# tube-control.net
KiCad netlist of a schematic drawn in Altium Designer
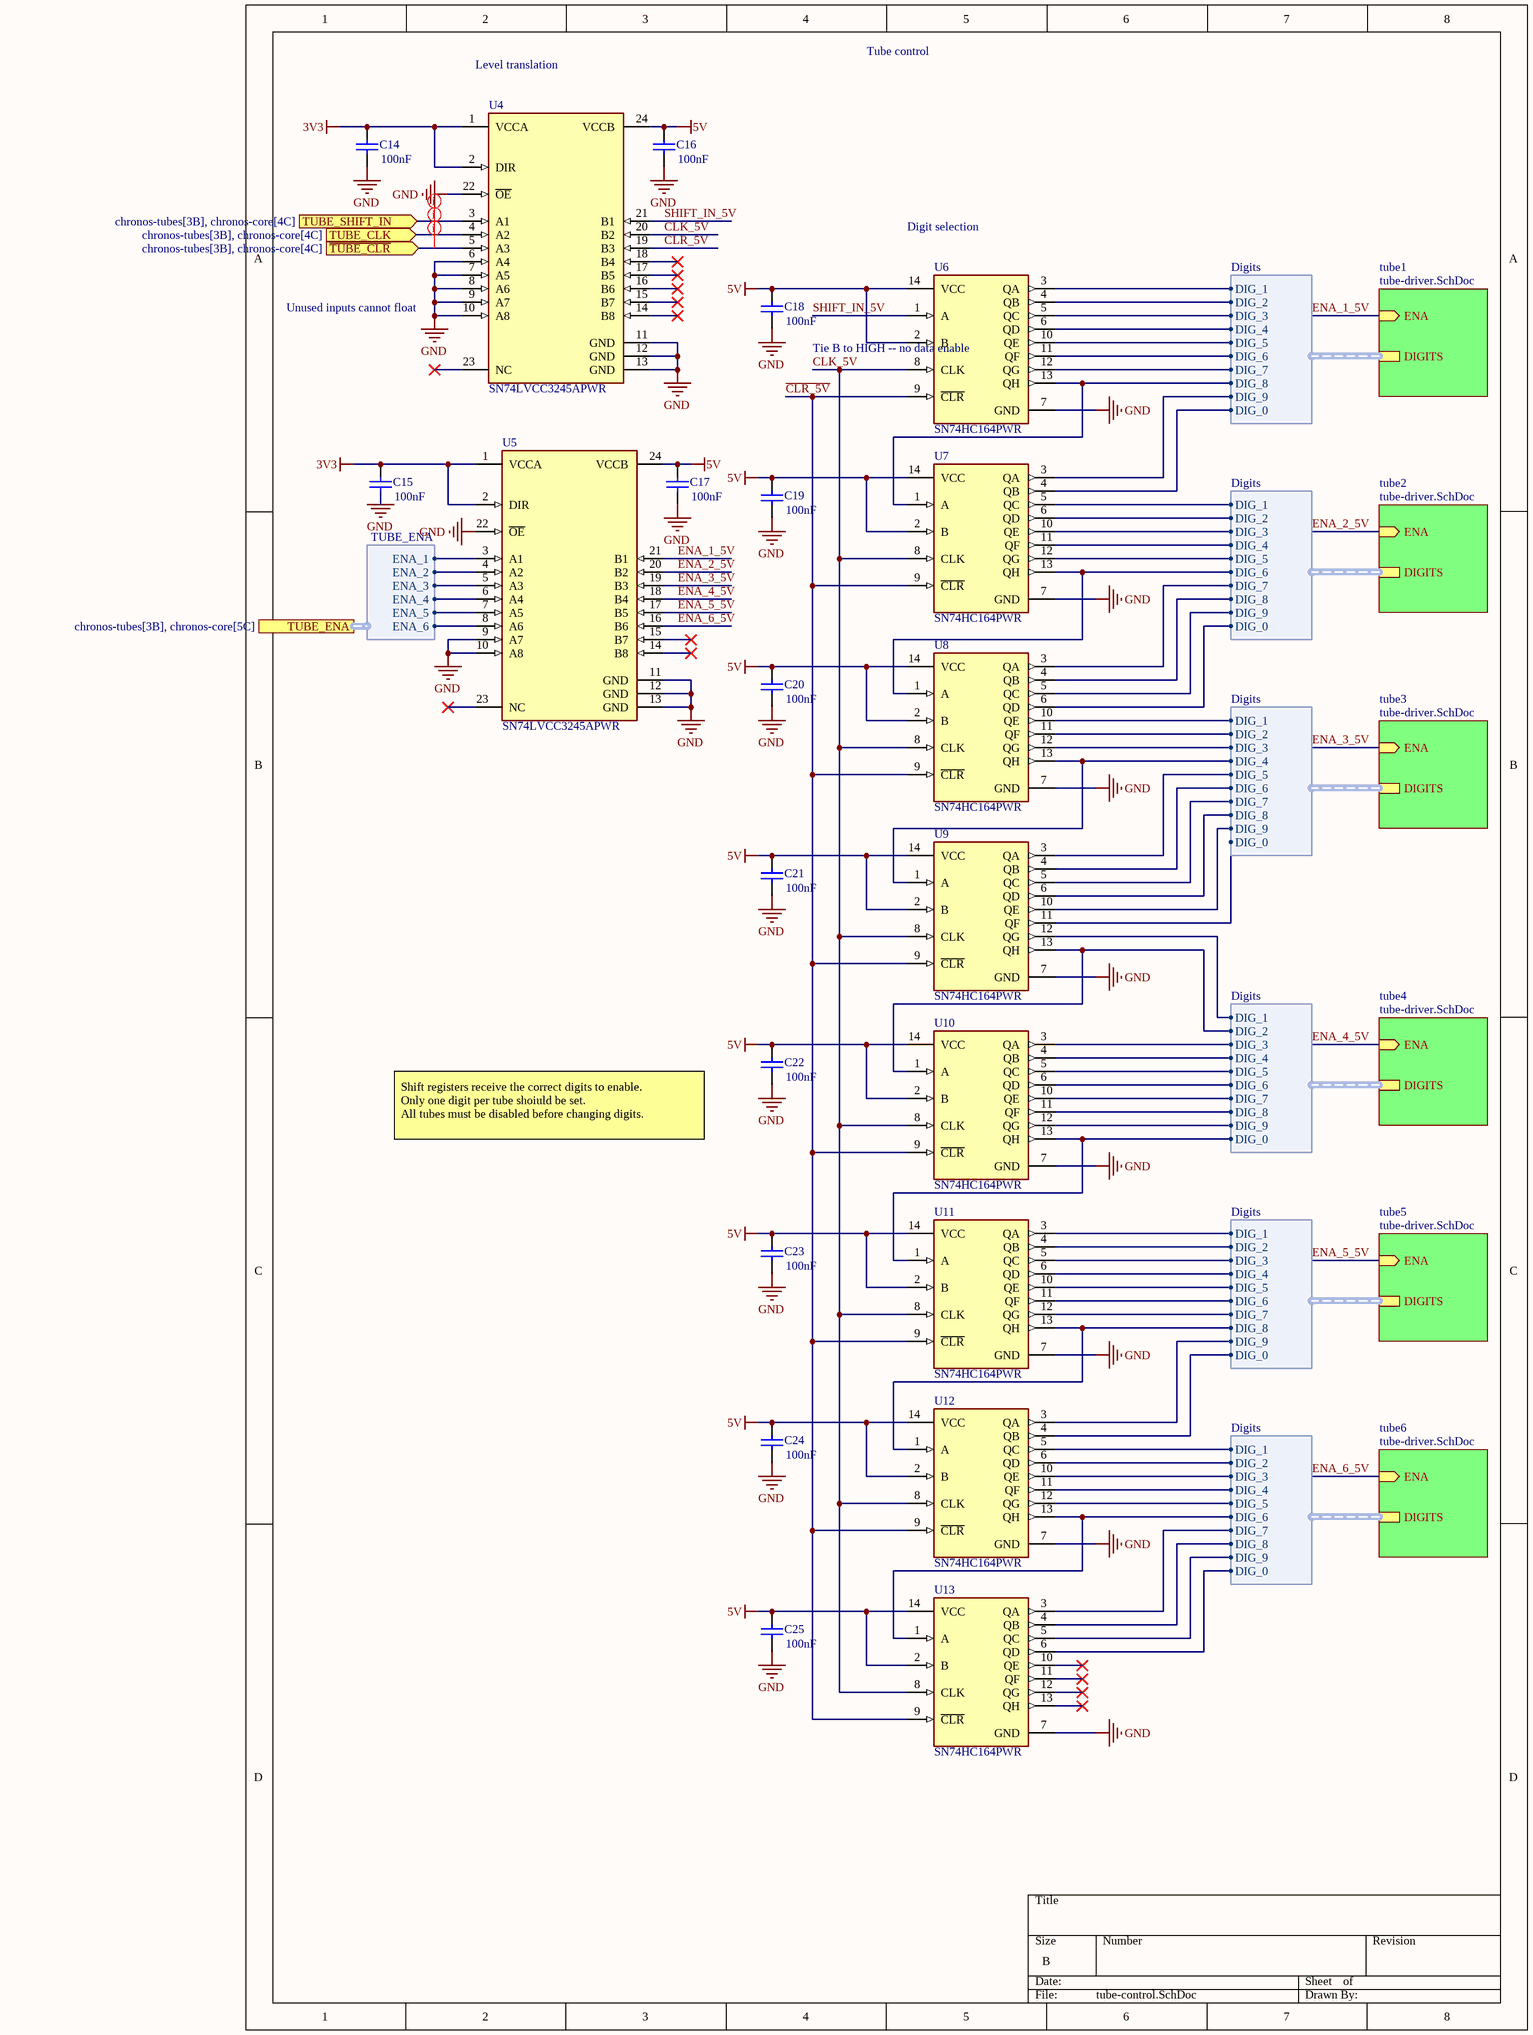
[diagram p0: tube-control.SchDoc]

(export (version "E")
  (design (tool "Eeschema 10.0.6"))
  (components
    (comp (ref "C14")
      (value "CL05B104KO5NNNC")
      (footprint "CAPC1050X55X23ML05T13")
      (description "Chip Capacitor, 100 nF, +/- 10%, 16 V, -55 to 125 degC, 0402 (1005 Metric), RoHS, Tape and Reel")
      (fields (field (name "MANUFACTURER") "Samsung Electro-Mechanics") (field (name "CAPACITANCE") "100nF"))
      (libsource (lib "Altium Content Vault") (part "CAP-NP-2"))
    )
    (comp (ref "C15")
      (value "CL05B104KO5NNNC")
      (footprint "CAPC1050X55X23ML05T13")
      (description "Chip Capacitor, 100 nF, +/- 10%, 16 V, -55 to 125 degC, 0402 (1005 Metric), RoHS, Tape and Reel")
      (fields (field (name "MANUFACTURER") "Samsung Electro-Mechanics") (field (name "CAPACITANCE") "100nF"))
      (libsource (lib "Altium Content Vault") (part "CAP-NP-2"))
    )
    (comp (ref "C16")
      (value "CL05B104KO5NNNC")
      (footprint "CAPC1050X55X23ML05T13")
      (description "Chip Capacitor, 100 nF, +/- 10%, 16 V, -55 to 125 degC, 0402 (1005 Metric), RoHS, Tape and Reel")
      (fields (field (name "MANUFACTURER") "Samsung Electro-Mechanics") (field (name "CAPACITANCE") "100nF"))
      (libsource (lib "Altium Content Vault") (part "CAP-NP-2"))
    )
    (comp (ref "C17")
      (value "CL05B104KO5NNNC")
      (footprint "CAPC1050X55X23ML05T13")
      (description "Chip Capacitor, 100 nF, +/- 10%, 16 V, -55 to 125 degC, 0402 (1005 Metric), RoHS, Tape and Reel")
      (fields (field (name "MANUFACTURER") "Samsung Electro-Mechanics") (field (name "CAPACITANCE") "100nF"))
      (libsource (lib "Altium Content Vault") (part "CAP-NP-2"))
    )
    (comp (ref "C18")
      (value "CL05B104KO5NNNC")
      (footprint "CAPC1050X55X23ML05T13")
      (description "Chip Capacitor, 100 nF, +/- 10%, 16 V, -55 to 125 degC, 0402 (1005 Metric), RoHS, Tape and Reel")
      (fields (field (name "MANUFACTURER") "Samsung Electro-Mechanics") (field (name "CAPACITANCE") "100nF"))
      (libsource (lib "Altium Content Vault") (part "CAP-NP-2"))
    )
    (comp (ref "C19")
      (value "CL05B104KO5NNNC")
      (footprint "CAPC1050X55X23ML05T13")
      (description "Chip Capacitor, 100 nF, +/- 10%, 16 V, -55 to 125 degC, 0402 (1005 Metric), RoHS, Tape and Reel")
      (fields (field (name "MANUFACTURER") "Samsung Electro-Mechanics") (field (name "CAPACITANCE") "100nF"))
      (libsource (lib "Altium Content Vault") (part "CAP-NP-2"))
    )
    (comp (ref "C20")
      (value "CL05B104KO5NNNC")
      (footprint "CAPC1050X55X23ML05T13")
      (description "Chip Capacitor, 100 nF, +/- 10%, 16 V, -55 to 125 degC, 0402 (1005 Metric), RoHS, Tape and Reel")
      (fields (field (name "MANUFACTURER") "Samsung Electro-Mechanics") (field (name "CAPACITANCE") "100nF"))
      (libsource (lib "Altium Content Vault") (part "CAP-NP-2"))
    )
    (comp (ref "C21")
      (value "CL05B104KO5NNNC")
      (footprint "CAPC1050X55X23ML05T13")
      (description "Chip Capacitor, 100 nF, +/- 10%, 16 V, -55 to 125 degC, 0402 (1005 Metric), RoHS, Tape and Reel")
      (fields (field (name "MANUFACTURER") "Samsung Electro-Mechanics") (field (name "CAPACITANCE") "100nF"))
      (libsource (lib "Altium Content Vault") (part "CAP-NP-2"))
    )
    (comp (ref "C22")
      (value "CL05B104KO5NNNC")
      (footprint "CAPC1050X55X23ML05T13")
      (description "Chip Capacitor, 100 nF, +/- 10%, 16 V, -55 to 125 degC, 0402 (1005 Metric), RoHS, Tape and Reel")
      (fields (field (name "MANUFACTURER") "Samsung Electro-Mechanics") (field (name "CAPACITANCE") "100nF"))
      (libsource (lib "Altium Content Vault") (part "CAP-NP-2"))
    )
    (comp (ref "C23")
      (value "CL05B104KO5NNNC")
      (footprint "CAPC1050X55X23ML05T13")
      (description "Chip Capacitor, 100 nF, +/- 10%, 16 V, -55 to 125 degC, 0402 (1005 Metric), RoHS, Tape and Reel")
      (fields (field (name "MANUFACTURER") "Samsung Electro-Mechanics") (field (name "CAPACITANCE") "100nF"))
      (libsource (lib "Altium Content Vault") (part "CAP-NP-2"))
    )
    (comp (ref "C24")
      (value "CL05B104KO5NNNC")
      (footprint "CAPC1050X55X23ML05T13")
      (description "Chip Capacitor, 100 nF, +/- 10%, 16 V, -55 to 125 degC, 0402 (1005 Metric), RoHS, Tape and Reel")
      (fields (field (name "MANUFACTURER") "Samsung Electro-Mechanics") (field (name "CAPACITANCE") "100nF"))
      (libsource (lib "Altium Content Vault") (part "CAP-NP-2"))
    )
    (comp (ref "C25")
      (value "CL05B104KO5NNNC")
      (footprint "CAPC1050X55X23ML05T13")
      (description "Chip Capacitor, 100 nF, +/- 10%, 16 V, -55 to 125 degC, 0402 (1005 Metric), RoHS, Tape and Reel")
      (fields (field (name "MANUFACTURER") "Samsung Electro-Mechanics") (field (name "CAPACITANCE") "100nF"))
      (libsource (lib "Altium Content Vault") (part "CAP-NP-2"))
    )
    (comp (ref "U4")
      (value "SN74LVCC3245APWR")
      (footprint "FP-PW0024A-MFG")
      (description "IC TRNSLTR BIDIRECTIONAL 24TSSOP")
      (fields
        (field (name "MANUFACTURER") "Texas Instruments")
        (field (name "OCTOPART") "https://octopart.com/sn74lvcc3245apwr-texas+instruments-517488")
      )
      (libsource (lib "Altium Content Vault") (part "b1748c378780dcaa776adbbcb5b9924"))
    )
    (comp (ref "U5")
      (value "SN74LVCC3245APWR")
      (footprint "FP-PW0024A-MFG")
      (description "IC TRNSLTR BIDIRECTIONAL 24TSSOP")
      (fields
        (field (name "MANUFACTURER") "Texas Instruments")
        (field (name "OCTOPART") "https://octopart.com/sn74lvcc3245apwr-texas+instruments-517488")
      )
      (libsource (lib "Altium Content Vault") (part "b1748c378780dcaa776adbbcb5b9924"))
    )
    (comp (ref "U6")
      (value "SN74HC164PWR")
      (footprint "FP-PW0014A-MFG")
      (description "IC SHFT REG SERIAL 8BIT 14-TSSOP")
      (fields
        (field (name "MANUFACTURER") "Texas Instruments")
        (field (name "OCTOPART") "https://octopart.com/sn74hc164pwr-texas+instruments-500613")
      )
      (libsource (lib "Altium Content Vault") (part "8ee7e56fdc1f52d79a3803b759dfdc3"))
    )
    (comp (ref "U7")
      (value "SN74HC164PWR")
      (footprint "FP-PW0014A-MFG")
      (description "IC SHFT REG SERIAL 8BIT 14-TSSOP")
      (fields
        (field (name "MANUFACTURER") "Texas Instruments")
        (field (name "OCTOPART") "https://octopart.com/sn74hc164pwr-texas+instruments-500613")
      )
      (libsource (lib "Altium Content Vault") (part "8ee7e56fdc1f52d79a3803b759dfdc3"))
    )
    (comp (ref "U8")
      (value "SN74HC164PWR")
      (footprint "FP-PW0014A-MFG")
      (description "IC SHFT REG SERIAL 8BIT 14-TSSOP")
      (fields
        (field (name "MANUFACTURER") "Texas Instruments")
        (field (name "OCTOPART") "https://octopart.com/sn74hc164pwr-texas+instruments-500613")
      )
      (libsource (lib "Altium Content Vault") (part "8ee7e56fdc1f52d79a3803b759dfdc3"))
    )
    (comp (ref "U9")
      (value "SN74HC164PWR")
      (footprint "FP-PW0014A-MFG")
      (description "IC SHFT REG SERIAL 8BIT 14-TSSOP")
      (fields
        (field (name "MANUFACTURER") "Texas Instruments")
        (field (name "OCTOPART") "https://octopart.com/sn74hc164pwr-texas+instruments-500613")
      )
      (libsource (lib "Altium Content Vault") (part "8ee7e56fdc1f52d79a3803b759dfdc3"))
    )
    (comp (ref "U10")
      (value "SN74HC164PWR")
      (footprint "FP-PW0014A-MFG")
      (description "IC SHFT REG SERIAL 8BIT 14-TSSOP")
      (fields
        (field (name "MANUFACTURER") "Texas Instruments")
        (field (name "OCTOPART") "https://octopart.com/sn74hc164pwr-texas+instruments-500613")
      )
      (libsource (lib "Altium Content Vault") (part "8ee7e56fdc1f52d79a3803b759dfdc3"))
    )
    (comp (ref "U11")
      (value "SN74HC164PWR")
      (footprint "FP-PW0014A-MFG")
      (description "IC SHFT REG SERIAL 8BIT 14-TSSOP")
      (fields
        (field (name "MANUFACTURER") "Texas Instruments")
        (field (name "OCTOPART") "https://octopart.com/sn74hc164pwr-texas+instruments-500613")
      )
      (libsource (lib "Altium Content Vault") (part "8ee7e56fdc1f52d79a3803b759dfdc3"))
    )
    (comp (ref "U12")
      (value "SN74HC164PWR")
      (footprint "FP-PW0014A-MFG")
      (description "IC SHFT REG SERIAL 8BIT 14-TSSOP")
      (fields
        (field (name "MANUFACTURER") "Texas Instruments")
        (field (name "OCTOPART") "https://octopart.com/sn74hc164pwr-texas+instruments-500613")
      )
      (libsource (lib "Altium Content Vault") (part "8ee7e56fdc1f52d79a3803b759dfdc3"))
    )
    (comp (ref "U13")
      (value "SN74HC164PWR")
      (footprint "FP-PW0014A-MFG")
      (description "IC SHFT REG SERIAL 8BIT 14-TSSOP")
      (fields
        (field (name "MANUFACTURER") "Texas Instruments")
        (field (name "OCTOPART") "https://octopart.com/sn74hc164pwr-texas+instruments-500613")
      )
      (libsource (lib "Altium Content Vault") (part "8ee7e56fdc1f52d79a3803b759dfdc3"))
    )
  )
  (nets
    (net (code "3") (name "/CLK_5V") (class "Default")
      (node (ref "U10") (pin "8") (pinfunction "CLK_8") (pintype "input"))
      (node (ref "U11") (pin "8") (pinfunction "CLK_8") (pintype "input"))
      (node (ref "U12") (pin "8") (pinfunction "CLK_8") (pintype "input"))
      (node (ref "U13") (pin "8") (pinfunction "CLK_8") (pintype "input"))
      (node (ref "U4") (pin "20") (pinfunction "B2_20") (pintype "input"))
      (node (ref "U6") (pin "8") (pinfunction "CLK_8") (pintype "input"))
      (node (ref "U7") (pin "8") (pinfunction "CLK_8") (pintype "input"))
      (node (ref "U8") (pin "8") (pinfunction "CLK_8") (pintype "input"))
      (node (ref "U9") (pin "8") (pinfunction "CLK_8") (pintype "input"))
    )
    (net (code "4") (name "/CLR_5V") (class "Default")
      (node (ref "U10") (pin "9") (pinfunction "~{CLR}_9") (pintype "input"))
      (node (ref "U11") (pin "9") (pinfunction "~{CLR}_9") (pintype "input"))
      (node (ref "U12") (pin "9") (pinfunction "~{CLR}_9") (pintype "input"))
      (node (ref "U13") (pin "9") (pinfunction "~{CLR}_9") (pintype "input"))
      (node (ref "U4") (pin "19") (pinfunction "B3_19") (pintype "input"))
      (node (ref "U6") (pin "9") (pinfunction "~{CLR}_9") (pintype "input"))
      (node (ref "U7") (pin "9") (pinfunction "~{CLR}_9") (pintype "input"))
      (node (ref "U8") (pin "9") (pinfunction "~{CLR}_9") (pintype "input"))
      (node (ref "U9") (pin "9") (pinfunction "~{CLR}_9") (pintype "input"))
    )
    (net (code "5") (name "/ENA_1") (class "Default")
      (node (ref "U5") (pin "3") (pinfunction "A1_3") (pintype "input"))
    )
    (net (code "6") (name "/ENA_1_5V") (class "Default")
      (node (ref "U5") (pin "21") (pinfunction "B1_21") (pintype "input"))
    )
    (net (code "7") (name "/ENA_2") (class "Default")
      (node (ref "U5") (pin "4") (pinfunction "A2_4") (pintype "input"))
    )
    (net (code "8") (name "/ENA_2_5V") (class "Default")
      (node (ref "U5") (pin "20") (pinfunction "B2_20") (pintype "input"))
    )
    (net (code "9") (name "/ENA_3") (class "Default")
      (node (ref "U5") (pin "5") (pinfunction "A3_5") (pintype "input"))
    )
    (net (code "10") (name "/ENA_3_5V") (class "Default")
      (node (ref "U5") (pin "19") (pinfunction "B3_19") (pintype "input"))
    )
    (net (code "11") (name "/ENA_4") (class "Default")
      (node (ref "U5") (pin "6") (pinfunction "A4_6") (pintype "input"))
    )
    (net (code "12") (name "/ENA_4_5V") (class "Default")
      (node (ref "U5") (pin "18") (pinfunction "B4_18") (pintype "input"))
    )
    (net (code "13") (name "/ENA_5") (class "Default")
      (node (ref "U5") (pin "7") (pinfunction "A5_7") (pintype "input"))
    )
    (net (code "14") (name "/ENA_5_5V") (class "Default")
      (node (ref "U5") (pin "17") (pinfunction "B5_17") (pintype "input"))
    )
    (net (code "15") (name "/ENA_6") (class "Default")
      (node (ref "U5") (pin "8") (pinfunction "A6_8") (pintype "input"))
    )
    (net (code "16") (name "/ENA_6_5V") (class "Default")
      (node (ref "U5") (pin "16") (pinfunction "B6_16") (pintype "input"))
    )
    (net (code "17") (name "/SHIFT_IN_5V") (class "Default")
      (node (ref "U4") (pin "21") (pinfunction "B1_21") (pintype "input"))
      (node (ref "U6") (pin "1") (pinfunction "A_1") (pintype "input"))
    )
    (net (code "18") (name "/TUBE_CLK") (class "Default")
      (node (ref "U4") (pin "4") (pinfunction "A2_4") (pintype "input"))
    )
    (net (code "19") (name "/TUBE_CLR") (class "Default")
      (node (ref "U4") (pin "5") (pinfunction "A3_5") (pintype "input"))
    )
    (net (code "20") (name "/TUBE_SHIFT_IN") (class "Default")
      (node (ref "U4") (pin "3") (pinfunction "A1_3") (pintype "input"))
    )
    (net (code "23") (name "3V3") (class "Default")
      (node (ref "C14") (pin "2") (pinfunction "2_2") (pintype "passive"))
      (node (ref "C15") (pin "2") (pinfunction "2_2") (pintype "passive"))
      (node (ref "U4") (pin "1") (pinfunction "VCCA_1") (pintype "power_in"))
      (node (ref "U4") (pin "2") (pinfunction "DIR_2") (pintype "input"))
      (node (ref "U5") (pin "1") (pinfunction "VCCA_1") (pintype "power_in"))
      (node (ref "U5") (pin "2") (pinfunction "DIR_2") (pintype "input"))
    )
    (net (code "24") (name "5V") (class "Default")
      (node (ref "C16") (pin "2") (pinfunction "2_2") (pintype "passive"))
      (node (ref "C17") (pin "2") (pinfunction "2_2") (pintype "passive"))
      (node (ref "C18") (pin "2") (pinfunction "2_2") (pintype "passive"))
      (node (ref "C19") (pin "2") (pinfunction "2_2") (pintype "passive"))
      (node (ref "C20") (pin "2") (pinfunction "2_2") (pintype "passive"))
      (node (ref "C21") (pin "2") (pinfunction "2_2") (pintype "passive"))
      (node (ref "C22") (pin "2") (pinfunction "2_2") (pintype "passive"))
      (node (ref "C23") (pin "2") (pinfunction "2_2") (pintype "passive"))
      (node (ref "C24") (pin "2") (pinfunction "2_2") (pintype "passive"))
      (node (ref "C25") (pin "2") (pinfunction "2_2") (pintype "passive"))
      (node (ref "U10") (pin "14") (pinfunction "VCC_14") (pintype "power_in"))
      (node (ref "U10") (pin "2") (pinfunction "B_2") (pintype "input"))
      (node (ref "U11") (pin "14") (pinfunction "VCC_14") (pintype "power_in"))
      (node (ref "U11") (pin "2") (pinfunction "B_2") (pintype "input"))
      (node (ref "U12") (pin "14") (pinfunction "VCC_14") (pintype "power_in"))
      (node (ref "U12") (pin "2") (pinfunction "B_2") (pintype "input"))
      (node (ref "U13") (pin "14") (pinfunction "VCC_14") (pintype "power_in"))
      (node (ref "U13") (pin "2") (pinfunction "B_2") (pintype "input"))
      (node (ref "U4") (pin "24") (pinfunction "VCCB_24") (pintype "power_in"))
      (node (ref "U5") (pin "24") (pinfunction "VCCB_24") (pintype "power_in"))
      (node (ref "U6") (pin "14") (pinfunction "VCC_14") (pintype "power_in"))
      (node (ref "U6") (pin "2") (pinfunction "B_2") (pintype "input"))
      (node (ref "U7") (pin "14") (pinfunction "VCC_14") (pintype "power_in"))
      (node (ref "U7") (pin "2") (pinfunction "B_2") (pintype "input"))
      (node (ref "U8") (pin "14") (pinfunction "VCC_14") (pintype "power_in"))
      (node (ref "U8") (pin "2") (pinfunction "B_2") (pintype "input"))
      (node (ref "U9") (pin "14") (pinfunction "VCC_14") (pintype "power_in"))
      (node (ref "U9") (pin "2") (pinfunction "B_2") (pintype "input"))
    )
    (net (code "25") (name "GND") (class "Default")
      (node (ref "C14") (pin "1") (pinfunction "1_1") (pintype "passive"))
      (node (ref "C15") (pin "1") (pinfunction "1_1") (pintype "passive"))
      (node (ref "C16") (pin "1") (pinfunction "1_1") (pintype "passive"))
      (node (ref "C17") (pin "1") (pinfunction "1_1") (pintype "passive"))
      (node (ref "C18") (pin "1") (pinfunction "1_1") (pintype "passive"))
      (node (ref "C19") (pin "1") (pinfunction "1_1") (pintype "passive"))
      (node (ref "C20") (pin "1") (pinfunction "1_1") (pintype "passive"))
      (node (ref "C21") (pin "1") (pinfunction "1_1") (pintype "passive"))
      (node (ref "C22") (pin "1") (pinfunction "1_1") (pintype "passive"))
      (node (ref "C23") (pin "1") (pinfunction "1_1") (pintype "passive"))
      (node (ref "C24") (pin "1") (pinfunction "1_1") (pintype "passive"))
      (node (ref "C25") (pin "1") (pinfunction "1_1") (pintype "passive"))
      (node (ref "U10") (pin "7") (pinfunction "GND_7") (pintype "power_in"))
      (node (ref "U11") (pin "7") (pinfunction "GND_7") (pintype "power_in"))
      (node (ref "U12") (pin "7") (pinfunction "GND_7") (pintype "power_in"))
      (node (ref "U13") (pin "7") (pinfunction "GND_7") (pintype "power_in"))
      (node (ref "U4") (pin "10") (pinfunction "A8_10") (pintype "input"))
      (node (ref "U4") (pin "11") (pinfunction "GND_11") (pintype "power_in"))
      (node (ref "U4") (pin "12") (pinfunction "GND_12") (pintype "power_in"))
      (node (ref "U4") (pin "13") (pinfunction "GND_13") (pintype "power_in"))
      (node (ref "U4") (pin "22") (pinfunction "~{OE}_22") (pintype "input"))
      (node (ref "U4") (pin "6") (pinfunction "A4_6") (pintype "input"))
      (node (ref "U4") (pin "7") (pinfunction "A5_7") (pintype "input"))
      (node (ref "U4") (pin "8") (pinfunction "A6_8") (pintype "input"))
      (node (ref "U4") (pin "9") (pinfunction "A7_9") (pintype "input"))
      (node (ref "U5") (pin "10") (pinfunction "A8_10") (pintype "input"))
      (node (ref "U5") (pin "11") (pinfunction "GND_11") (pintype "power_in"))
      (node (ref "U5") (pin "12") (pinfunction "GND_12") (pintype "power_in"))
      (node (ref "U5") (pin "13") (pinfunction "GND_13") (pintype "power_in"))
      (node (ref "U5") (pin "22") (pinfunction "~{OE}_22") (pintype "input"))
      (node (ref "U5") (pin "9") (pinfunction "A7_9") (pintype "input"))
      (node (ref "U6") (pin "7") (pinfunction "GND_7") (pintype "power_in"))
      (node (ref "U7") (pin "7") (pinfunction "GND_7") (pintype "power_in"))
      (node (ref "U8") (pin "7") (pinfunction "GND_7") (pintype "power_in"))
      (node (ref "U9") (pin "7") (pinfunction "GND_7") (pintype "power_in"))
    )
    (net (code "26") (name "Net-(U6-QH)") (class "Default")
      (node (ref "U6") (pin "13") (pinfunction "QH_13") (pintype "output"))
      (node (ref "U7") (pin "1") (pinfunction "A_1") (pintype "input"))
    )
    (net (code "27") (name "Net-(U7-QH)") (class "Default")
      (node (ref "U7") (pin "13") (pinfunction "QH_13") (pintype "output"))
      (node (ref "U8") (pin "1") (pinfunction "A_1") (pintype "input"))
    )
    (net (code "28") (name "Net-(U8-QH)") (class "Default")
      (node (ref "U8") (pin "13") (pinfunction "QH_13") (pintype "output"))
      (node (ref "U9") (pin "1") (pinfunction "A_1") (pintype "input"))
    )
    (net (code "29") (name "Net-(U10-A)") (class "Default")
      (node (ref "U10") (pin "1") (pinfunction "A_1") (pintype "input"))
      (node (ref "U9") (pin "13") (pinfunction "QH_13") (pintype "output"))
    )
    (net (code "30") (name "Net-(U10-QH)") (class "Default")
      (node (ref "U10") (pin "13") (pinfunction "QH_13") (pintype "output"))
      (node (ref "U11") (pin "1") (pinfunction "A_1") (pintype "input"))
    )
    (net (code "31") (name "Net-(U11-QH)") (class "Default")
      (node (ref "U11") (pin "13") (pinfunction "QH_13") (pintype "output"))
      (node (ref "U12") (pin "1") (pinfunction "A_1") (pintype "input"))
    )
    (net (code "32") (name "Net-(U12-QH)") (class "Default")
      (node (ref "U12") (pin "13") (pinfunction "QH_13") (pintype "output"))
      (node (ref "U13") (pin "1") (pinfunction "A_1") (pintype "input"))
    )
    (net (code "33") (name "unconnected-(U4-B4-Pad18)") (class "Default")
      (node (ref "U4") (pin "18") (pinfunction "B4_18") (pintype "input+no_connect"))
    )
    (net (code "34") (name "unconnected-(U4-B5-Pad17)") (class "Default")
      (node (ref "U4") (pin "17") (pinfunction "B5_17") (pintype "input+no_connect"))
    )
    (net (code "35") (name "unconnected-(U4-B6-Pad16)") (class "Default")
      (node (ref "U4") (pin "16") (pinfunction "B6_16") (pintype "input+no_connect"))
    )
    (net (code "36") (name "unconnected-(U4-B7-Pad15)") (class "Default")
      (node (ref "U4") (pin "15") (pinfunction "B7_15") (pintype "input+no_connect"))
    )
    (net (code "37") (name "unconnected-(U4-B8-Pad14)") (class "Default")
      (node (ref "U4") (pin "14") (pinfunction "B8_14") (pintype "input+no_connect"))
    )
    (net (code "38") (name "unconnected-(U4-NC-Pad23)") (class "Default")
      (node (ref "U4") (pin "23") (pinfunction "NC_23") (pintype "passive+no_connect"))
    )
    (net (code "39") (name "unconnected-(U5-B7-Pad15)") (class "Default")
      (node (ref "U5") (pin "15") (pinfunction "B7_15") (pintype "input+no_connect"))
    )
    (net (code "40") (name "unconnected-(U5-B8-Pad14)") (class "Default")
      (node (ref "U5") (pin "14") (pinfunction "B8_14") (pintype "input+no_connect"))
    )
    (net (code "41") (name "unconnected-(U5-NC-Pad23)") (class "Default")
      (node (ref "U5") (pin "23") (pinfunction "NC_23") (pintype "passive+no_connect"))
    )
    (net (code "42") (name "unconnected-(U6-QA-Pad3)") (class "Default")
      (node (ref "U6") (pin "3") (pinfunction "QA_3") (pintype "output"))
    )
    (net (code "43") (name "unconnected-(U6-QB-Pad4)") (class "Default")
      (node (ref "U6") (pin "4") (pinfunction "QB_4") (pintype "output"))
    )
    (net (code "44") (name "unconnected-(U6-QC-Pad5)") (class "Default")
      (node (ref "U6") (pin "5") (pinfunction "QC_5") (pintype "output"))
    )
    (net (code "45") (name "unconnected-(U6-QD-Pad6)") (class "Default")
      (node (ref "U6") (pin "6") (pinfunction "QD_6") (pintype "output"))
    )
    (net (code "46") (name "unconnected-(U6-QE-Pad10)") (class "Default")
      (node (ref "U6") (pin "10") (pinfunction "QE_10") (pintype "output"))
    )
    (net (code "47") (name "unconnected-(U6-QF-Pad11)") (class "Default")
      (node (ref "U6") (pin "11") (pinfunction "QF_11") (pintype "output"))
    )
    (net (code "48") (name "unconnected-(U6-QG-Pad12)") (class "Default")
      (node (ref "U6") (pin "12") (pinfunction "QG_12") (pintype "output"))
    )
    (net (code "49") (name "unconnected-(U7-QA-Pad3)") (class "Default")
      (node (ref "U7") (pin "3") (pinfunction "QA_3") (pintype "output"))
    )
    (net (code "50") (name "unconnected-(U7-QB-Pad4)") (class "Default")
      (node (ref "U7") (pin "4") (pinfunction "QB_4") (pintype "output"))
    )
    (net (code "51") (name "unconnected-(U7-QC-Pad5)") (class "Default")
      (node (ref "U7") (pin "5") (pinfunction "QC_5") (pintype "output"))
    )
    (net (code "52") (name "unconnected-(U7-QD-Pad6)") (class "Default")
      (node (ref "U7") (pin "6") (pinfunction "QD_6") (pintype "output"))
    )
    (net (code "53") (name "unconnected-(U7-QE-Pad10)") (class "Default")
      (node (ref "U7") (pin "10") (pinfunction "QE_10") (pintype "output"))
    )
    (net (code "54") (name "unconnected-(U7-QF-Pad11)") (class "Default")
      (node (ref "U7") (pin "11") (pinfunction "QF_11") (pintype "output"))
    )
    (net (code "55") (name "unconnected-(U7-QG-Pad12)") (class "Default")
      (node (ref "U7") (pin "12") (pinfunction "QG_12") (pintype "output"))
    )
    (net (code "56") (name "unconnected-(U8-QA-Pad3)") (class "Default")
      (node (ref "U8") (pin "3") (pinfunction "QA_3") (pintype "output"))
    )
    (net (code "57") (name "unconnected-(U8-QB-Pad4)") (class "Default")
      (node (ref "U8") (pin "4") (pinfunction "QB_4") (pintype "output"))
    )
    (net (code "58") (name "unconnected-(U8-QC-Pad5)") (class "Default")
      (node (ref "U8") (pin "5") (pinfunction "QC_5") (pintype "output"))
    )
    (net (code "59") (name "unconnected-(U8-QD-Pad6)") (class "Default")
      (node (ref "U8") (pin "6") (pinfunction "QD_6") (pintype "output"))
    )
    (net (code "60") (name "unconnected-(U8-QE-Pad10)") (class "Default")
      (node (ref "U8") (pin "10") (pinfunction "QE_10") (pintype "output"))
    )
    (net (code "61") (name "unconnected-(U8-QF-Pad11)") (class "Default")
      (node (ref "U8") (pin "11") (pinfunction "QF_11") (pintype "output"))
    )
    (net (code "62") (name "unconnected-(U8-QG-Pad12)") (class "Default")
      (node (ref "U8") (pin "12") (pinfunction "QG_12") (pintype "output"))
    )
    (net (code "63") (name "unconnected-(U9-QA-Pad3)") (class "Default")
      (node (ref "U9") (pin "3") (pinfunction "QA_3") (pintype "output"))
    )
    (net (code "64") (name "unconnected-(U9-QB-Pad4)") (class "Default")
      (node (ref "U9") (pin "4") (pinfunction "QB_4") (pintype "output"))
    )
    (net (code "65") (name "unconnected-(U9-QC-Pad5)") (class "Default")
      (node (ref "U9") (pin "5") (pinfunction "QC_5") (pintype "output"))
    )
    (net (code "66") (name "unconnected-(U9-QD-Pad6)") (class "Default")
      (node (ref "U9") (pin "6") (pinfunction "QD_6") (pintype "output"))
    )
    (net (code "67") (name "unconnected-(U9-QE-Pad10)") (class "Default")
      (node (ref "U9") (pin "10") (pinfunction "QE_10") (pintype "output"))
    )
    (net (code "68") (name "unconnected-(U9-QF-Pad11)") (class "Default")
      (node (ref "U9") (pin "11") (pinfunction "QF_11") (pintype "output"))
    )
    (net (code "69") (name "unconnected-(U9-QG-Pad12)") (class "Default")
      (node (ref "U9") (pin "12") (pinfunction "QG_12") (pintype "output"))
    )
    (net (code "70") (name "unconnected-(U10-QA-Pad3)") (class "Default")
      (node (ref "U10") (pin "3") (pinfunction "QA_3") (pintype "output"))
    )
    (net (code "71") (name "unconnected-(U10-QB-Pad4)") (class "Default")
      (node (ref "U10") (pin "4") (pinfunction "QB_4") (pintype "output"))
    )
    (net (code "72") (name "unconnected-(U10-QC-Pad5)") (class "Default")
      (node (ref "U10") (pin "5") (pinfunction "QC_5") (pintype "output"))
    )
    (net (code "73") (name "unconnected-(U10-QD-Pad6)") (class "Default")
      (node (ref "U10") (pin "6") (pinfunction "QD_6") (pintype "output"))
    )
    (net (code "74") (name "unconnected-(U10-QE-Pad10)") (class "Default")
      (node (ref "U10") (pin "10") (pinfunction "QE_10") (pintype "output"))
    )
    (net (code "75") (name "unconnected-(U10-QF-Pad11)") (class "Default")
      (node (ref "U10") (pin "11") (pinfunction "QF_11") (pintype "output"))
    )
    (net (code "76") (name "unconnected-(U10-QG-Pad12)") (class "Default")
      (node (ref "U10") (pin "12") (pinfunction "QG_12") (pintype "output"))
    )
    (net (code "77") (name "unconnected-(U11-QA-Pad3)") (class "Default")
      (node (ref "U11") (pin "3") (pinfunction "QA_3") (pintype "output"))
    )
    (net (code "78") (name "unconnected-(U11-QB-Pad4)") (class "Default")
      (node (ref "U11") (pin "4") (pinfunction "QB_4") (pintype "output"))
    )
    (net (code "79") (name "unconnected-(U11-QC-Pad5)") (class "Default")
      (node (ref "U11") (pin "5") (pinfunction "QC_5") (pintype "output"))
    )
    (net (code "80") (name "unconnected-(U11-QD-Pad6)") (class "Default")
      (node (ref "U11") (pin "6") (pinfunction "QD_6") (pintype "output"))
    )
    (net (code "81") (name "unconnected-(U11-QE-Pad10)") (class "Default")
      (node (ref "U11") (pin "10") (pinfunction "QE_10") (pintype "output"))
    )
    (net (code "82") (name "unconnected-(U11-QF-Pad11)") (class "Default")
      (node (ref "U11") (pin "11") (pinfunction "QF_11") (pintype "output"))
    )
    (net (code "83") (name "unconnected-(U11-QG-Pad12)") (class "Default")
      (node (ref "U11") (pin "12") (pinfunction "QG_12") (pintype "output"))
    )
    (net (code "84") (name "unconnected-(U12-QA-Pad3)") (class "Default")
      (node (ref "U12") (pin "3") (pinfunction "QA_3") (pintype "output"))
    )
    (net (code "85") (name "unconnected-(U12-QB-Pad4)") (class "Default")
      (node (ref "U12") (pin "4") (pinfunction "QB_4") (pintype "output"))
    )
    (net (code "86") (name "unconnected-(U12-QC-Pad5)") (class "Default")
      (node (ref "U12") (pin "5") (pinfunction "QC_5") (pintype "output"))
    )
    (net (code "87") (name "unconnected-(U12-QD-Pad6)") (class "Default")
      (node (ref "U12") (pin "6") (pinfunction "QD_6") (pintype "output"))
    )
    (net (code "88") (name "unconnected-(U12-QE-Pad10)") (class "Default")
      (node (ref "U12") (pin "10") (pinfunction "QE_10") (pintype "output"))
    )
    (net (code "89") (name "unconnected-(U12-QF-Pad11)") (class "Default")
      (node (ref "U12") (pin "11") (pinfunction "QF_11") (pintype "output"))
    )
    (net (code "90") (name "unconnected-(U12-QG-Pad12)") (class "Default")
      (node (ref "U12") (pin "12") (pinfunction "QG_12") (pintype "output"))
    )
    (net (code "91") (name "unconnected-(U13-QA-Pad3)") (class "Default")
      (node (ref "U13") (pin "3") (pinfunction "QA_3") (pintype "output"))
    )
    (net (code "92") (name "unconnected-(U13-QB-Pad4)") (class "Default")
      (node (ref "U13") (pin "4") (pinfunction "QB_4") (pintype "output"))
    )
    (net (code "93") (name "unconnected-(U13-QC-Pad5)") (class "Default")
      (node (ref "U13") (pin "5") (pinfunction "QC_5") (pintype "output"))
    )
    (net (code "94") (name "unconnected-(U13-QD-Pad6)") (class "Default")
      (node (ref "U13") (pin "6") (pinfunction "QD_6") (pintype "output"))
    )
    (net (code "95") (name "unconnected-(U13-QE-Pad10)") (class "Default")
      (node (ref "U13") (pin "10") (pinfunction "QE_10") (pintype "output+no_connect"))
    )
    (net (code "96") (name "unconnected-(U13-QF-Pad11)") (class "Default")
      (node (ref "U13") (pin "11") (pinfunction "QF_11") (pintype "output+no_connect"))
    )
    (net (code "97") (name "unconnected-(U13-QG-Pad12)") (class "Default")
      (node (ref "U13") (pin "12") (pinfunction "QG_12") (pintype "output+no_connect"))
    )
    (net (code "98") (name "unconnected-(U13-QH-Pad13)") (class "Default")
      (node (ref "U13") (pin "13") (pinfunction "QH_13") (pintype "output+no_connect"))
    )
  )
)
